# pwr_misc.net
KiCad netlist of a schematic drawn in Altium Designer
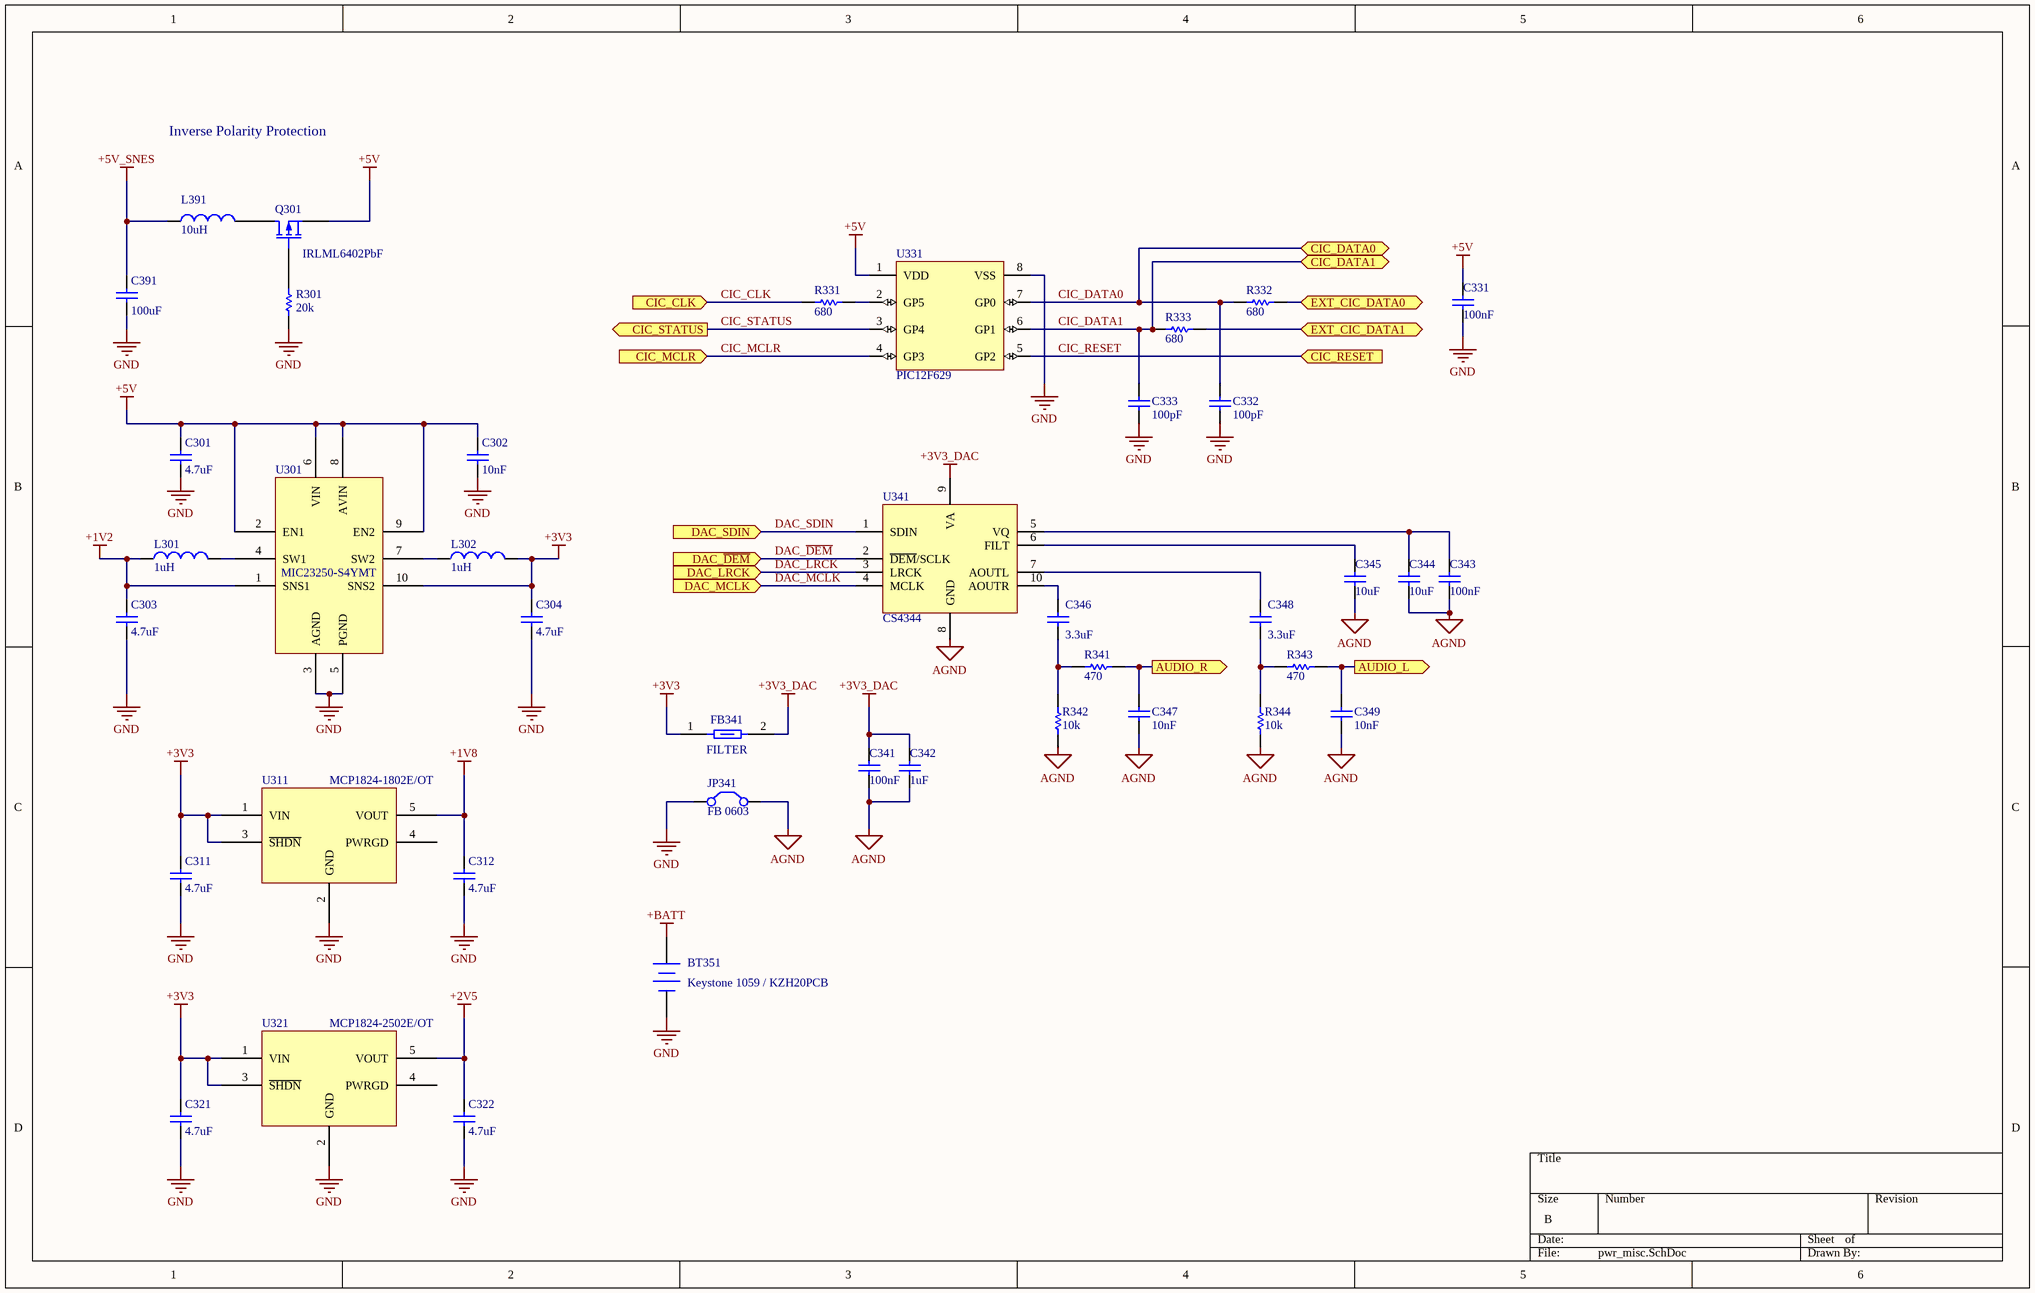
[diagram p0: pwr_misc.SchDoc]

(export (version "E")
  (design (tool "Eeschema 10.0.6"))
  (components
    (comp (ref "BT351")
      (value "Keystone 1059 / KZH20PCB")
      (footprint "BT_KEYSTONE_1059_20MM")
      (description "Battery")
      (libsource (lib "Miscellaneous Devices") (part "Battery"))
    )
    (comp (ref "C301")
      (value "4.7uF")
      (footprint "SM0805")
      (description "Capacitor")
      (libsource (lib "Miscellaneous Devices") (part "Cap"))
    )
    (comp (ref "C302")
      (value "10nF")
      (footprint "SM0805")
      (description "Capacitor")
      (libsource (lib "Miscellaneous Devices") (part "Cap"))
    )
    (comp (ref "C303")
      (value "4.7uF")
      (footprint "SM0805")
      (description "Capacitor")
      (libsource (lib "Miscellaneous Devices") (part "Cap"))
    )
    (comp (ref "C304")
      (value "4.7uF")
      (footprint "SM0805")
      (description "Capacitor")
      (libsource (lib "Miscellaneous Devices") (part "Cap"))
    )
    (comp (ref "C311")
      (value "4.7uF")
      (footprint "SM0805")
      (description "Capacitor")
      (libsource (lib "Miscellaneous Devices") (part "Cap"))
    )
    (comp (ref "C312")
      (value "4.7uF")
      (footprint "SM0805")
      (description "Capacitor")
      (libsource (lib "Miscellaneous Devices") (part "Cap"))
    )
    (comp (ref "C321")
      (value "4.7uF")
      (footprint "SM0805")
      (description "Capacitor")
      (libsource (lib "Miscellaneous Devices") (part "Cap"))
    )
    (comp (ref "C322")
      (value "4.7uF")
      (footprint "SM0805")
      (description "Capacitor")
      (libsource (lib "Miscellaneous Devices") (part "Cap"))
    )
    (comp (ref "C331")
      (value "100nF")
      (footprint "SM0805")
      (description "Capacitor")
      (libsource (lib "Miscellaneous Devices") (part "Cap"))
    )
    (comp (ref "C332")
      (value "100pF")
      (footprint "SM0805")
      (description "Capacitor")
      (libsource (lib "Miscellaneous Devices") (part "Cap"))
    )
    (comp (ref "C333")
      (value "100pF")
      (footprint "SM0805")
      (description "Capacitor")
      (libsource (lib "Miscellaneous Devices") (part "Cap"))
    )
    (comp (ref "C341")
      (value "100nF")
      (footprint "SM0805")
      (description "Capacitor")
      (libsource (lib "Miscellaneous Devices") (part "Cap"))
    )
    (comp (ref "C342")
      (value "1uF")
      (footprint "SM0805")
      (description "Capacitor")
      (libsource (lib "Miscellaneous Devices") (part "Cap"))
    )
    (comp (ref "C343")
      (value "100nF")
      (footprint "SM0805")
      (description "Capacitor")
      (libsource (lib "Miscellaneous Devices") (part "Cap"))
    )
    (comp (ref "C344")
      (value "10uF")
      (footprint "SM0805")
      (description "Capacitor")
      (libsource (lib "Miscellaneous Devices") (part "Cap"))
    )
    (comp (ref "C345")
      (value "10uF")
      (footprint "SM0805")
      (description "Capacitor")
      (libsource (lib "Miscellaneous Devices") (part "Cap"))
    )
    (comp (ref "C346")
      (value "3.3uF")
      (footprint "SM0805")
      (description "Capacitor")
      (libsource (lib "Miscellaneous Devices") (part "Cap"))
    )
    (comp (ref "C347")
      (value "10nF")
      (footprint "SM0805")
      (description "Capacitor")
      (libsource (lib "Miscellaneous Devices") (part "Cap"))
    )
    (comp (ref "C348")
      (value "3.3uF")
      (footprint "SM0805")
      (description "Capacitor")
      (libsource (lib "Miscellaneous Devices") (part "Cap"))
    )
    (comp (ref "C349")
      (value "10nF")
      (footprint "SM0805")
      (description "Capacitor")
      (libsource (lib "Miscellaneous Devices") (part "Cap"))
    )
    (comp (ref "C391")
      (value "100uF")
      (footprint "SM1210")
      (description "Capacitor")
      (libsource (lib "Miscellaneous Devices") (part "Cap"))
    )
    (comp (ref "FB341") (value "FILTER") (footprint "SM0805") (libsource (lib "Schlib1") (part "FILTER")))
    (comp (ref "JP341")
      (value "FB 0603")
      (footprint "JUMPER")
      (description "Jumper Wire")
      (libsource (lib "Miscellaneous Devices") (part "Jumper"))
    )
    (comp (ref "L301")
      (value "1uH")
      (footprint "SM1210L")
      (description "Inductor")
      (libsource (lib "Miscellaneous Devices") (part "Inductor"))
    )
    (comp (ref "L302")
      (value "1uH")
      (footprint "SM1210L")
      (description "Inductor")
      (libsource (lib "Miscellaneous Devices") (part "Inductor"))
    )
    (comp (ref "L391")
      (value "10uH")
      (footprint "SM1210L")
      (description "Inductor")
      (libsource (lib "Miscellaneous Devices") (part "Inductor"))
    )
    (comp (ref "Q301")
      (value "IRLML6402PbF")
      (footprint "SOT23DGS")
      (description "P-Channel MOSFET")
      (libsource (lib "Miscellaneous Devices") (part "MOSFET-P"))
    )
    (comp (ref "R301")
      (value "20k")
      (footprint "SM0805")
      (description "Resistor")
      (libsource (lib "Miscellaneous Devices") (part "Res1"))
    )
    (comp (ref "R331")
      (value "680")
      (footprint "SM0805")
      (description "Resistor")
      (libsource (lib "Miscellaneous Devices") (part "Res1"))
    )
    (comp (ref "R332")
      (value "680")
      (footprint "SM0805")
      (description "Resistor")
      (libsource (lib "Miscellaneous Devices") (part "Res1"))
    )
    (comp (ref "R333")
      (value "680")
      (footprint "SM0805")
      (description "Resistor")
      (libsource (lib "Miscellaneous Devices") (part "Res1"))
    )
    (comp (ref "R341")
      (value "470")
      (footprint "SM0805")
      (description "Resistor")
      (libsource (lib "Miscellaneous Devices") (part "Res1"))
    )
    (comp (ref "R342")
      (value "10k")
      (footprint "SM0805")
      (description "Resistor")
      (libsource (lib "Miscellaneous Devices") (part "Res1"))
    )
    (comp (ref "R343")
      (value "470")
      (footprint "SM0805")
      (description "Resistor")
      (libsource (lib "Miscellaneous Devices") (part "Res1"))
    )
    (comp (ref "R344")
      (value "10k")
      (footprint "SM0805")
      (description "Resistor")
      (libsource (lib "Miscellaneous Devices") (part "Res1"))
    )
    (comp (ref "U301")
      (value "MIC23250-S4YMT")
      (footprint "QFN10-2x2_LONGPADS")
      (libsource (lib "Schlib1") (part "MIC23250-S4YMT"))
    )
    (comp (ref "U311")
      (value "MCP1824-1802E/OT")
      (footprint "SOT23-5_LARGEPADS")
      (description "MCP1824")
      (libsource (lib "Schlib1") (part "MCP1824"))
    )
    (comp (ref "U321")
      (value "MCP1824-2502E/OT")
      (footprint "SOT23-5_LARGEPADS")
      (description "MCP1824")
      (libsource (lib "Schlib1") (part "MCP1824"))
    )
    (comp (ref "U331")
      (value "PIC12F629")
      (footprint "DIP-8__300")
      (libsource (lib "Schlib1") (part "PIC12F629"))
    )
    (comp (ref "U341") (value "CS4344") (footprint "TSSOP10") (libsource (lib "Schlib1") (part "CS4344")))
  )
  (nets
    (net (code "1") (name "+1V2") (class "Default")
      (node (ref "C303") (pin "1") (pinfunction "1_1") (pintype "passive"))
      (node (ref "L301") (pin "1") (pinfunction "1_1") (pintype "passive"))
      (node (ref "U301") (pin "1") (pinfunction "SNS1_1") (pintype "passive"))
    )
    (net (code "2") (name "+1V8") (class "Default")
      (node (ref "C312") (pin "1") (pinfunction "1_1") (pintype "passive"))
      (node (ref "U311") (pin "5") (pinfunction "VOUT_5") (pintype "passive"))
    )
    (net (code "3") (name "+2V5") (class "Default")
      (node (ref "C322") (pin "1") (pinfunction "1_1") (pintype "passive"))
      (node (ref "U321") (pin "5") (pinfunction "VOUT_5") (pintype "passive"))
    )
    (net (code "4") (name "+3V3") (class "Default")
      (node (ref "C304") (pin "1") (pinfunction "1_1") (pintype "passive"))
      (node (ref "C311") (pin "1") (pinfunction "1_1") (pintype "passive"))
      (node (ref "C321") (pin "1") (pinfunction "1_1") (pintype "passive"))
      (node (ref "FB341") (pin "1") (pinfunction "1_1") (pintype "passive"))
      (node (ref "L302") (pin "2") (pinfunction "2_2") (pintype "passive"))
      (node (ref "U301") (pin "10") (pinfunction "SNS2_10") (pintype "passive"))
      (node (ref "U311") (pin "1") (pinfunction "VIN_1") (pintype "passive"))
      (node (ref "U311") (pin "3") (pinfunction "~{SHDN}_3") (pintype "passive"))
      (node (ref "U321") (pin "1") (pinfunction "VIN_1") (pintype "passive"))
      (node (ref "U321") (pin "3") (pinfunction "~{SHDN}_3") (pintype "passive"))
    )
    (net (code "5") (name "+3V3_DAC") (class "Default")
      (node (ref "C341") (pin "1") (pinfunction "1_1") (pintype "passive"))
      (node (ref "C342") (pin "1") (pinfunction "1_1") (pintype "passive"))
      (node (ref "FB341") (pin "2") (pinfunction "2_2") (pintype "passive"))
      (node (ref "U341") (pin "9") (pinfunction "VA_9") (pintype "passive"))
    )
    (net (code "6") (name "+5V") (class "Default")
      (node (ref "C301") (pin "1") (pinfunction "1_1") (pintype "passive"))
      (node (ref "C302") (pin "1") (pinfunction "1_1") (pintype "passive"))
      (node (ref "C331") (pin "1") (pinfunction "1_1") (pintype "passive"))
      (node (ref "Q301") (pin "3") (pinfunction "S_3") (pintype "passive"))
      (node (ref "U301") (pin "2") (pinfunction "EN1_2") (pintype "passive"))
      (node (ref "U301") (pin "6") (pinfunction "VIN_6") (pintype "passive"))
      (node (ref "U301") (pin "8") (pinfunction "AVIN_8") (pintype "passive"))
      (node (ref "U301") (pin "9") (pinfunction "EN2_9") (pintype "passive"))
      (node (ref "U331") (pin "1") (pinfunction "VDD_1") (pintype "power_in"))
    )
    (net (code "7") (name "+5V_SNES") (class "Default")
      (node (ref "C391") (pin "1") (pinfunction "1_1") (pintype "passive"))
      (node (ref "L391") (pin "1") (pinfunction "1_1") (pintype "passive"))
    )
    (net (code "8") (name "+BATT") (class "Default")
      (node (ref "BT351") (pin "1") (pinfunction "+_1") (pintype "passive"))
    )
    (net (code "9") (name "/AUDIO_L") (class "Default")
      (node (ref "C349") (pin "1") (pinfunction "1_1") (pintype "passive"))
      (node (ref "R343") (pin "1") (pinfunction "1_1") (pintype "passive"))
    )
    (net (code "10") (name "/AUDIO_R") (class "Default")
      (node (ref "C347") (pin "1") (pinfunction "1_1") (pintype "passive"))
      (node (ref "R341") (pin "1") (pinfunction "1_1") (pintype "passive"))
    )
    (net (code "11") (name "/CIC_CLK") (class "Default")
      (node (ref "R331") (pin "2") (pinfunction "2_2") (pintype "passive"))
    )
    (net (code "12") (name "/CIC_DATA0") (class "Default")
      (node (ref "C332") (pin "1") (pinfunction "1_1") (pintype "passive"))
      (node (ref "R332") (pin "1") (pinfunction "1_1") (pintype "passive"))
      (node (ref "U331") (pin "7") (pinfunction "GP0_7") (pintype "bidirectional"))
    )
    (net (code "13") (name "/CIC_DATA1") (class "Default")
      (node (ref "C333") (pin "1") (pinfunction "1_1") (pintype "passive"))
      (node (ref "R333") (pin "2") (pinfunction "2_2") (pintype "passive"))
      (node (ref "U331") (pin "6") (pinfunction "GP1_6") (pintype "bidirectional"))
    )
    (net (code "14") (name "/CIC_MCLR") (class "Default")
      (node (ref "U331") (pin "4") (pinfunction "GP3_4") (pintype "bidirectional"))
    )
    (net (code "15") (name "/CIC_RESET") (class "Default")
      (node (ref "U331") (pin "5") (pinfunction "GP2_5") (pintype "bidirectional"))
    )
    (net (code "16") (name "/CIC_STATUS") (class "Default")
      (node (ref "U331") (pin "3") (pinfunction "GP4_3") (pintype "bidirectional"))
    )
    (net (code "17") (name "/DAC_LRCK") (class "Default")
      (node (ref "U341") (pin "3") (pinfunction "LRCK_3") (pintype "passive"))
    )
    (net (code "18") (name "/DAC_MCLK") (class "Default")
      (node (ref "U341") (pin "4") (pinfunction "MCLK_4") (pintype "passive"))
    )
    (net (code "19") (name "/DAC_SDIN") (class "Default")
      (node (ref "U341") (pin "1") (pinfunction "SDIN_1") (pintype "passive"))
    )
    (net (code "20") (name "/DAC_~{DEM}") (class "Default")
      (node (ref "U341") (pin "2") (pinfunction "~{DEM}/SCLK_2") (pintype "passive"))
    )
    (net (code "21") (name "/EXT_CIC_DATA0") (class "Default")
      (node (ref "R332") (pin "2") (pinfunction "2_2") (pintype "passive"))
    )
    (net (code "22") (name "/EXT_CIC_DATA1") (class "Default")
      (node (ref "R333") (pin "1") (pinfunction "1_1") (pintype "passive"))
    )
    (net (code "23") (name "AGND") (class "Default")
      (node (ref "C341") (pin "2") (pinfunction "2_2") (pintype "passive"))
      (node (ref "C342") (pin "2") (pinfunction "2_2") (pintype "passive"))
      (node (ref "C343") (pin "2") (pinfunction "2_2") (pintype "passive"))
      (node (ref "C344") (pin "2") (pinfunction "2_2") (pintype "passive"))
      (node (ref "C345") (pin "2") (pinfunction "2_2") (pintype "passive"))
      (node (ref "C347") (pin "2") (pinfunction "2_2") (pintype "passive"))
      (node (ref "C349") (pin "2") (pinfunction "2_2") (pintype "passive"))
      (node (ref "JP341") (pin "2") (pinfunction "C2_2") (pintype "passive"))
      (node (ref "R342") (pin "2") (pinfunction "2_2") (pintype "passive"))
      (node (ref "R344") (pin "2") (pinfunction "2_2") (pintype "passive"))
      (node (ref "U341") (pin "8") (pinfunction "GND_8") (pintype "passive"))
    )
    (net (code "24") (name "GND") (class "Default")
      (node (ref "BT351") (pin "2") (pinfunction "-_2") (pintype "passive"))
      (node (ref "C301") (pin "2") (pinfunction "2_2") (pintype "passive"))
      (node (ref "C302") (pin "2") (pinfunction "2_2") (pintype "passive"))
      (node (ref "C303") (pin "2") (pinfunction "2_2") (pintype "passive"))
      (node (ref "C304") (pin "2") (pinfunction "2_2") (pintype "passive"))
      (node (ref "C311") (pin "2") (pinfunction "2_2") (pintype "passive"))
      (node (ref "C312") (pin "2") (pinfunction "2_2") (pintype "passive"))
      (node (ref "C321") (pin "2") (pinfunction "2_2") (pintype "passive"))
      (node (ref "C322") (pin "2") (pinfunction "2_2") (pintype "passive"))
      (node (ref "C331") (pin "2") (pinfunction "2_2") (pintype "passive"))
      (node (ref "C332") (pin "2") (pinfunction "2_2") (pintype "passive"))
      (node (ref "C333") (pin "2") (pinfunction "2_2") (pintype "passive"))
      (node (ref "C391") (pin "2") (pinfunction "2_2") (pintype "passive"))
      (node (ref "JP341") (pin "1") (pinfunction "C1_1") (pintype "passive"))
      (node (ref "R301") (pin "1") (pinfunction "1_1") (pintype "passive"))
      (node (ref "U301") (pin "3") (pinfunction "AGND_3") (pintype "passive"))
      (node (ref "U301") (pin "5") (pinfunction "PGND_5") (pintype "passive"))
      (node (ref "U311") (pin "2") (pinfunction "GND_2") (pintype "passive"))
      (node (ref "U321") (pin "2") (pinfunction "GND_2") (pintype "passive"))
      (node (ref "U331") (pin "8") (pinfunction "VSS_8") (pintype "power_in"))
    )
    (net (code "25") (name "Net-(C346-Pad1)") (class "Default")
      (node (ref "C346") (pin "1") (pinfunction "1_1") (pintype "passive"))
      (node (ref "R341") (pin "2") (pinfunction "2_2") (pintype "passive"))
      (node (ref "R342") (pin "1") (pinfunction "1_1") (pintype "passive"))
    )
    (net (code "26") (name "Net-(C348-Pad1)") (class "Default")
      (node (ref "C348") (pin "1") (pinfunction "1_1") (pintype "passive"))
      (node (ref "R343") (pin "2") (pinfunction "2_2") (pintype "passive"))
      (node (ref "R344") (pin "1") (pinfunction "1_1") (pintype "passive"))
    )
    (net (code "27") (name "Net-(Q301-D)") (class "Default")
      (node (ref "L391") (pin "2") (pinfunction "2_2") (pintype "passive"))
      (node (ref "Q301") (pin "1") (pinfunction "D_1") (pintype "passive"))
    )
    (net (code "28") (name "Net-(Q301-G)") (class "Default")
      (node (ref "Q301") (pin "2") (pinfunction "G_2") (pintype "passive"))
      (node (ref "R301") (pin "2") (pinfunction "2_2") (pintype "passive"))
    )
    (net (code "29") (name "Net-(U301-SW1)") (class "Default")
      (node (ref "L301") (pin "2") (pinfunction "2_2") (pintype "passive"))
      (node (ref "U301") (pin "4") (pinfunction "SW1_4") (pintype "passive"))
    )
    (net (code "30") (name "Net-(U301-SW2)") (class "Default")
      (node (ref "L302") (pin "1") (pinfunction "1_1") (pintype "passive"))
      (node (ref "U301") (pin "7") (pinfunction "SW2_7") (pintype "passive"))
    )
    (net (code "31") (name "Net-(U331-GP5)") (class "Default")
      (node (ref "R331") (pin "1") (pinfunction "1_1") (pintype "passive"))
      (node (ref "U331") (pin "2") (pinfunction "GP5_2") (pintype "bidirectional"))
    )
    (net (code "32") (name "Net-(U341-AOUTL)") (class "Default")
      (node (ref "C348") (pin "2") (pinfunction "2_2") (pintype "passive"))
      (node (ref "U341") (pin "7") (pinfunction "AOUTL_7") (pintype "passive"))
    )
    (net (code "33") (name "Net-(U341-AOUTR)") (class "Default")
      (node (ref "C346") (pin "2") (pinfunction "2_2") (pintype "passive"))
      (node (ref "U341") (pin "10") (pinfunction "AOUTR_10") (pintype "passive"))
    )
    (net (code "34") (name "Net-(U341-FILT)") (class "Default")
      (node (ref "C345") (pin "1") (pinfunction "1_1") (pintype "passive"))
      (node (ref "U341") (pin "6") (pinfunction "FILT_6") (pintype "passive"))
    )
    (net (code "35") (name "Net-(U341-VQ)") (class "Default")
      (node (ref "C343") (pin "1") (pinfunction "1_1") (pintype "passive"))
      (node (ref "C344") (pin "1") (pinfunction "1_1") (pintype "passive"))
      (node (ref "U341") (pin "5") (pinfunction "VQ_5") (pintype "passive"))
    )
    (net (code "36") (name "unconnected-(U311-PWRGD-Pad4)") (class "Default")
      (node (ref "U311") (pin "4") (pinfunction "PWRGD_4") (pintype "passive"))
    )
    (net (code "37") (name "unconnected-(U321-PWRGD-Pad4)") (class "Default")
      (node (ref "U321") (pin "4") (pinfunction "PWRGD_4") (pintype "passive"))
    )
  )
)
